# TrinketBlinkM0N.net
KiCad netlist of a schematic drawn in EAGLE
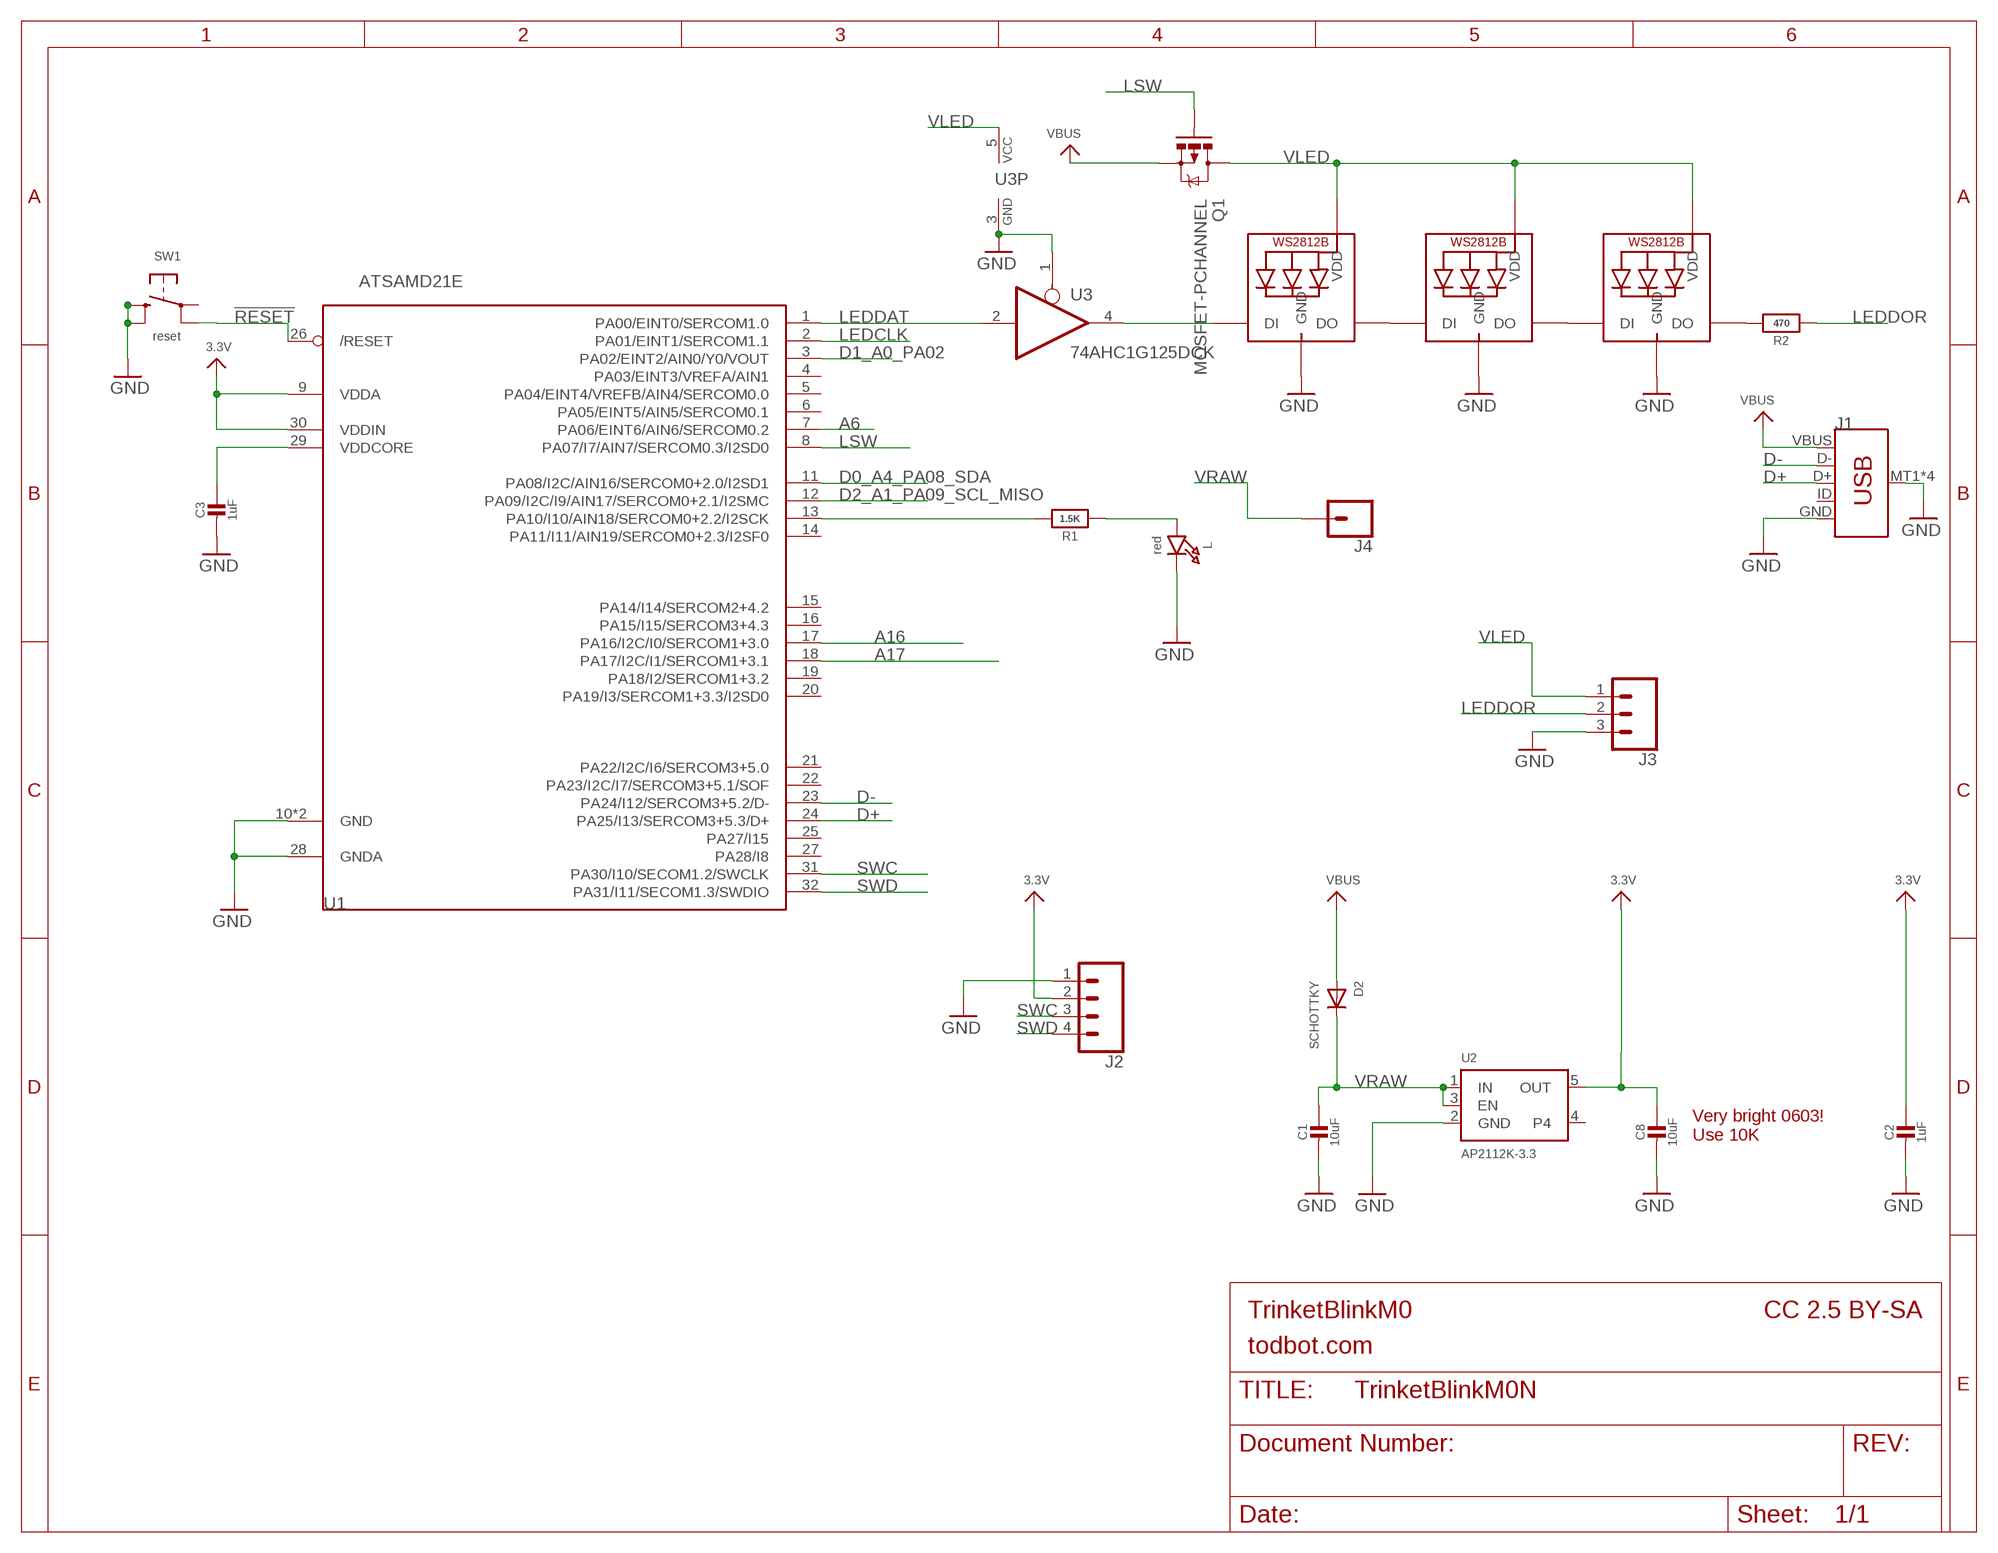
[diagram p0: schematic, sheet 1]

(export (version "E")
  (design (tool "Eeschema 10.0.6"))
  (components
    (comp (ref "C1")
      (value "10uF")
      (footprint "eagle-import:0805-NO")
      (libsource (lib "eagle-import") (part "CAP_CERAMIC0805-NOOUTLINE"))
    )
    (comp (ref "C2")
      (value "1uF")
      (footprint "eagle-import:0603-NO")
      (libsource (lib "eagle-import") (part "CAP_CERAMIC0603_NO"))
    )
    (comp (ref "C3")
      (value "1uF")
      (footprint "eagle-import:0603-NO")
      (libsource (lib "eagle-import") (part "CAP_CERAMIC0603_NO"))
    )
    (comp (ref "C8")
      (value "10uF")
      (footprint "eagle-import:0805-NO")
      (libsource (lib "eagle-import") (part "CAP_CERAMIC0805-NOOUTLINE"))
    )
    (comp (ref "D2")
      (value "SCHOTTKY")
      (footprint "eagle-import:SOD-123FL")
      (libsource (lib "eagle-import") (part "DIODE_SOD-123FL"))
    )
    (comp (ref "J1")
      (value "USB_MICRO-B_SMT")
      (footprint "eagle-import:USB-MICROB")
      (libsource (lib "eagle-import") (part "USB_MICRO-B_SMT"))
    )
    (comp (ref "J2")
      (value "CONN_04")
      (footprint "eagle-import:1X04")
      (libsource (lib "eagle-import") (part "CONN_04"))
    )
    (comp (ref "J3")
      (value "CONN_03")
      (footprint "eagle-import:1X03")
      (libsource (lib "eagle-import") (part "CONN_03"))
    )
    (comp (ref "J4")
      (value "CONN_01")
      (footprint "eagle-import:1X01")
      (libsource (lib "eagle-import") (part "CONN_01"))
    )
    (comp (ref "L")
      (value "red")
      (footprint "eagle-import:CHIPLED_0603_NOOUTLINE")
      (libsource (lib "eagle-import") (part "LED0603_NOOUTLINE"))
    )
    (comp (ref "LED1")
      (value "WS2812B3535")
      (footprint "eagle-import:LED3535")
      (libsource (lib "eagle-import") (part "WS2812B3535"))
    )
    (comp (ref "LED2")
      (value "WS2812B3535")
      (footprint "eagle-import:LED3535")
      (libsource (lib "eagle-import") (part "WS2812B3535"))
    )
    (comp (ref "LED3")
      (value "WS2812B3535")
      (footprint "eagle-import:LED3535")
      (libsource (lib "eagle-import") (part "WS2812B3535"))
    )
    (comp (ref "Q1")
      (value "MOSFET-PCHANNEL")
      (footprint "eagle-import:SOT23-3")
      (libsource (lib "eagle-import") (part "MOSFET-PCHANNEL"))
    )
    (comp (ref "R1")
      (value "1.5K")
      (footprint "eagle-import:0603-NO")
      (libsource (lib "eagle-import") (part "RESISTOR_0603_NOOUT"))
    )
    (comp (ref "R2")
      (value "470")
      (footprint "eagle-import:0603-NO")
      (libsource (lib "eagle-import") (part "RESISTOR_0603_NOOUT"))
    )
    (comp (ref "SW1")
      (value "reset")
      (footprint "eagle-import:BTN_KMR2_4.6X2.8")
      (libsource (lib "eagle-import") (part "SWITCH_TACT_SMT4.6X2.8"))
    )
    (comp (ref "U1")
      (value "ATSAMD21E")
      (footprint "eagle-import:QFN32_5MM")
      (libsource (lib "eagle-import") (part "ATSAMD21E"))
    )
    (comp (ref "U2")
      (value "AP2112K-3.3")
      (footprint "eagle-import:SOT23-5")
      (libsource (lib "eagle-import") (part "VREG_SOT23-5"))
    )
    (comp (ref "U3")
      (value "74AHC1G125DCK")
      (footprint "eagle-import:SC70-5")
      (libsource (lib "eagle-import") (part "741G125DCKAHC"))
    )
  )
  (nets
    (net (code "1") (name "/A6") (class "Default")
      (node (ref "U1") (pin "7") (pinfunction "PA06/EINT6/AIN6/SERCOM0.2_7") (pintype "bidirectional"))
    )
    (net (code "2") (name "/A16") (class "Default")
      (node (ref "U1") (pin "17") (pinfunction "PA16/I2C/I0/SERCOM1+3.0_17") (pintype "bidirectional"))
    )
    (net (code "3") (name "/A17") (class "Default")
      (node (ref "U1") (pin "18") (pinfunction "PA17/I2C/I1/SERCOM1+3.1_18") (pintype "bidirectional"))
    )
    (net (code "4") (name "/D+") (class "Default")
      (node (ref "J1") (pin "D+") (pinfunction "D+_D+") (pintype "bidirectional"))
      (node (ref "U1") (pin "24") (pinfunction "PA25/I13/SERCOM3+5.3/D+_24") (pintype "bidirectional"))
    )
    (net (code "5") (name "/D-") (class "Default")
      (node (ref "J1") (pin "D-") (pinfunction "D-_D-") (pintype "bidirectional"))
      (node (ref "U1") (pin "23") (pinfunction "PA24/I12/SERCOM3+5.2/D-_23") (pintype "bidirectional"))
    )
    (net (code "6") (name "/D0_A4_PA08_SDA") (class "Default")
      (node (ref "U1") (pin "11") (pinfunction "PA08/I2C/AIN16/SERCOM0+2.0/I2SD1_11") (pintype "bidirectional"))
    )
    (net (code "7") (name "/D1_A0_PA02") (class "Default")
      (node (ref "U1") (pin "3") (pinfunction "PA02/EINT2/AIN0/Y0/VOUT_3") (pintype "bidirectional"))
    )
    (net (code "8") (name "/D2_A1_PA09_SCL_MISO") (class "Default")
      (node (ref "U1") (pin "12") (pinfunction "PA09/I2C/I9/AIN17/SERCOM0+2.1/I2SMC_12") (pintype "bidirectional"))
    )
    (net (code "9") (name "/LEDCLK") (class "Default")
      (node (ref "U1") (pin "2") (pinfunction "PA01/EINT1/SERCOM1.1_2") (pintype "bidirectional"))
    )
    (net (code "10") (name "/LEDDAT") (class "Default")
      (node (ref "U1") (pin "1") (pinfunction "PA00/EINT0/SERCOM1.0_1") (pintype "bidirectional"))
      (node (ref "U3") (pin "2") (pinfunction "I_2") (pintype "input"))
    )
    (net (code "11") (name "/LEDDOR") (class "Default")
      (node (ref "J3") (pin "2") (pinfunction "2_2") (pintype "passive"))
      (node (ref "R2") (pin "1") (pinfunction "1_1") (pintype "passive"))
    )
    (net (code "12") (name "/LSW") (class "Default")
      (node (ref "Q1") (pin "1") (pinfunction "G_1") (pintype "passive"))
      (node (ref "U1") (pin "8") (pinfunction "PA07/I7/AIN7/SERCOM0.3/I2SD0_8") (pintype "bidirectional"))
    )
    (net (code "13") (name "/SWC") (class "Default")
      (node (ref "J2") (pin "3") (pinfunction "3_3") (pintype "passive"))
      (node (ref "U1") (pin "31") (pinfunction "PA30/I10/SECOM1.2/SWCLK_31") (pintype "bidirectional"))
    )
    (net (code "14") (name "/SWD") (class "Default")
      (node (ref "J2") (pin "4") (pinfunction "4_4") (pintype "passive"))
      (node (ref "U1") (pin "32") (pinfunction "PA31/I11/SECOM1.3/SWDIO_32") (pintype "bidirectional"))
    )
    (net (code "15") (name "/VLED") (class "Default")
      (node (ref "J3") (pin "1") (pinfunction "1_1") (pintype "passive"))
      (node (ref "LED1") (pin "2") (pinfunction "VDD_2") (pintype "power_in"))
      (node (ref "LED2") (pin "2") (pinfunction "VDD_2") (pintype "power_in"))
      (node (ref "LED3") (pin "2") (pinfunction "VDD_2") (pintype "power_in"))
      (node (ref "Q1") (pin "3") (pinfunction "D_3") (pintype "passive"))
      (node (ref "U3") (pin "5") (pinfunction "VCC_5") (pintype "power_in"))
    )
    (net (code "16") (name "/VRAW") (class "Default")
      (node (ref "C1") (pin "1") (pinfunction "1_1") (pintype "passive"))
      (node (ref "D2") (pin "C") (pinfunction "C_C") (pintype "passive"))
      (node (ref "J4") (pin "1") (pinfunction "1_1") (pintype "passive"))
      (node (ref "U2") (pin "1") (pinfunction "IN_1") (pintype "power_in"))
      (node (ref "U2") (pin "3") (pinfunction "EN_3") (pintype "input"))
    )
    (net (code "17") (name "/~{RESET}") (class "Default")
      (node (ref "SW1") (pin "A'") (pinfunction "P1_A'") (pintype "passive"))
      (node (ref "U1") (pin "26") (pinfunction "/RESET_26") (pintype "bidirectional"))
    )
    (net (code "18") (name "3.3V") (class "Default")
      (node (ref "C2") (pin "1") (pinfunction "1_1") (pintype "passive"))
      (node (ref "C8") (pin "1") (pinfunction "1_1") (pintype "passive"))
      (node (ref "J2") (pin "2") (pinfunction "2_2") (pintype "passive"))
      (node (ref "U1") (pin "30") (pinfunction "VDDIN_30") (pintype "power_in"))
      (node (ref "U1") (pin "9") (pinfunction "VDDA_9") (pintype "power_in"))
      (node (ref "U2") (pin "5") (pinfunction "OUT_5") (pintype "power_in"))
    )
    (net (code "19") (name "GND") (class "Default")
      (node (ref "C1") (pin "2") (pinfunction "2_2") (pintype "passive"))
      (node (ref "C2") (pin "2") (pinfunction "2_2") (pintype "passive"))
      (node (ref "C3") (pin "2") (pinfunction "2_2") (pintype "passive"))
      (node (ref "C8") (pin "2") (pinfunction "2_2") (pintype "passive"))
      (node (ref "J1") (pin "GND") (pinfunction "GND_GND") (pintype "power_in"))
      (node (ref "J1") (pin "MT1") (pinfunction "SHIELD_MT1") (pintype "bidirectional"))
      (node (ref "J1") (pin "MT2") (pinfunction "SHIELD_MT2") (pintype "bidirectional"))
      (node (ref "J1") (pin "P$1") (pinfunction "SHIELD_P$1") (pintype "bidirectional"))
      (node (ref "J1") (pin "P$2") (pinfunction "SHIELD_P$2") (pintype "bidirectional"))
      (node (ref "J2") (pin "1") (pinfunction "1_1") (pintype "passive"))
      (node (ref "J3") (pin "3") (pinfunction "3_3") (pintype "passive"))
      (node (ref "L") (pin "C") (pinfunction "C_C") (pintype "passive"))
      (node (ref "LED1") (pin "4") (pinfunction "GND_4") (pintype "power_in"))
      (node (ref "LED2") (pin "4") (pinfunction "GND_4") (pintype "power_in"))
      (node (ref "LED3") (pin "4") (pinfunction "GND_4") (pintype "power_in"))
      (node (ref "SW1") (pin "B") (pinfunction "S_B") (pintype "passive"))
      (node (ref "SW1") (pin "B'") (pinfunction "S1_B'") (pintype "passive"))
      (node (ref "U1") (pin "10") (pinfunction "GND_10") (pintype "power_in"))
      (node (ref "U1") (pin "28") (pinfunction "GNDA_28") (pintype "power_in"))
      (node (ref "U1") (pin "33") (pinfunction "GND_33") (pintype "power_in"))
      (node (ref "U2") (pin "2") (pinfunction "GND_2") (pintype "power_in"))
      (node (ref "U3") (pin "1") (pinfunction "OE_1") (pintype "input"))
      (node (ref "U3") (pin "3") (pinfunction "GND_3") (pintype "power_in"))
    )
    (net (code "20") (name "Net-(L-PadA)") (class "Default")
      (node (ref "L") (pin "A") (pinfunction "A_A") (pintype "passive"))
      (node (ref "R1") (pin "1") (pinfunction "1_1") (pintype "passive"))
    )
    (net (code "21") (name "Net-(LED1-DI)") (class "Default")
      (node (ref "LED1") (pin "1") (pinfunction "DI_1") (pintype "input"))
      (node (ref "U3") (pin "4") (pinfunction "O_4") (pintype "tri_state"))
    )
    (net (code "22") (name "Net-(LED1-DO)") (class "Default")
      (node (ref "LED1") (pin "3") (pinfunction "DO_3") (pintype "output"))
      (node (ref "LED2") (pin "1") (pinfunction "DI_1") (pintype "input"))
    )
    (net (code "23") (name "Net-(LED2-DO)") (class "Default")
      (node (ref "LED2") (pin "3") (pinfunction "DO_3") (pintype "output"))
      (node (ref "LED3") (pin "1") (pinfunction "DI_1") (pintype "input"))
    )
    (net (code "24") (name "Net-(LED3-DO)") (class "Default")
      (node (ref "LED3") (pin "3") (pinfunction "DO_3") (pintype "output"))
      (node (ref "R2") (pin "2") (pinfunction "2_2") (pintype "passive"))
    )
    (net (code "25") (name "Net-(U1-PA10{slash}I10{slash}AIN18{slash}SERCOM0+2.2{slash}I2SCK)") (class "Default")
      (node (ref "R1") (pin "2") (pinfunction "2_2") (pintype "passive"))
      (node (ref "U1") (pin "13") (pinfunction "PA10/I10/AIN18/SERCOM0+2.2/I2SCK_13") (pintype "bidirectional"))
    )
    (net (code "26") (name "Net-(U1-VDDCORE)") (class "Default")
      (node (ref "C3") (pin "1") (pinfunction "1_1") (pintype "passive"))
      (node (ref "U1") (pin "29") (pinfunction "VDDCORE_29") (pintype "power_in"))
    )
    (net (code "27") (name "VBUS") (class "Default")
      (node (ref "D2") (pin "A") (pinfunction "A_A") (pintype "passive"))
      (node (ref "J1") (pin "VBUS") (pinfunction "VBUS_VBUS") (pintype "power_in"))
      (node (ref "Q1") (pin "2") (pinfunction "S_2") (pintype "passive"))
    )
    (net (code "28") (name "unconnected-(J1-PadID)") (class "Default")
      (node (ref "J1") (pin "ID") (pinfunction "ID_ID") (pintype "bidirectional"))
    )
    (net (code "29") (name "unconnected-(SW1-P-PadA)") (class "Default")
      (node (ref "SW1") (pin "A") (pinfunction "P_A") (pintype "passive"))
    )
    (net (code "30") (name "unconnected-(U1-PA03{slash}EINT3{slash}VREFA{slash}AIN1-Pad4)") (class "Default")
      (node (ref "U1") (pin "4") (pinfunction "PA03/EINT3/VREFA/AIN1_4") (pintype "bidirectional"))
    )
    (net (code "31") (name "unconnected-(U1-PA04{slash}EINT4{slash}VREFB{slash}AIN4{slash}SERCOM0.0-Pad5)") (class "Default")
      (node (ref "U1") (pin "5") (pinfunction "PA04/EINT4/VREFB/AIN4/SERCOM0.0_5") (pintype "bidirectional"))
    )
    (net (code "32") (name "unconnected-(U1-PA05{slash}EINT5{slash}AIN5{slash}SERCOM0.1-Pad6)") (class "Default")
      (node (ref "U1") (pin "6") (pinfunction "PA05/EINT5/AIN5/SERCOM0.1_6") (pintype "bidirectional"))
    )
    (net (code "33") (name "unconnected-(U1-PA11{slash}I11{slash}AIN19{slash}SERCOM0+2.3{slash}I2SF0-Pad14)") (class "Default")
      (node (ref "U1") (pin "14") (pinfunction "PA11/I11/AIN19/SERCOM0+2.3/I2SF0_14") (pintype "bidirectional"))
    )
    (net (code "34") (name "unconnected-(U1-PA14{slash}I14{slash}SERCOM2+4.2-Pad15)") (class "Default")
      (node (ref "U1") (pin "15") (pinfunction "PA14/I14/SERCOM2+4.2_15") (pintype "bidirectional"))
    )
    (net (code "35") (name "unconnected-(U1-PA15{slash}I15{slash}SERCOM3+4.3-Pad16)") (class "Default")
      (node (ref "U1") (pin "16") (pinfunction "PA15/I15/SERCOM3+4.3_16") (pintype "bidirectional"))
    )
    (net (code "36") (name "unconnected-(U1-PA18{slash}I2{slash}SERCOM1+3.2-Pad19)") (class "Default")
      (node (ref "U1") (pin "19") (pinfunction "PA18/I2/SERCOM1+3.2_19") (pintype "bidirectional"))
    )
    (net (code "37") (name "unconnected-(U1-PA19{slash}I3{slash}SERCOM1+3.3{slash}I2SD0-Pad20)") (class "Default")
      (node (ref "U1") (pin "20") (pinfunction "PA19/I3/SERCOM1+3.3/I2SD0_20") (pintype "bidirectional"))
    )
    (net (code "38") (name "unconnected-(U1-PA22{slash}I2C{slash}I6{slash}SERCOM3+5.0-Pad21)") (class "Default")
      (node (ref "U1") (pin "21") (pinfunction "PA22/I2C/I6/SERCOM3+5.0_21") (pintype "bidirectional"))
    )
    (net (code "39") (name "unconnected-(U1-PA23{slash}I2C{slash}I7{slash}SERCOM3+5.1{slash}SOF-Pad22)") (class "Default")
      (node (ref "U1") (pin "22") (pinfunction "PA23/I2C/I7/SERCOM3+5.1/SOF_22") (pintype "bidirectional"))
    )
    (net (code "40") (name "unconnected-(U1-PA27{slash}I15-Pad25)") (class "Default")
      (node (ref "U1") (pin "25") (pinfunction "PA27/I15_25") (pintype "bidirectional"))
    )
    (net (code "41") (name "unconnected-(U1-PA28{slash}I8-Pad27)") (class "Default")
      (node (ref "U1") (pin "27") (pinfunction "PA28/I8_27") (pintype "bidirectional"))
    )
    (net (code "42") (name "unconnected-(U2-P4-Pad4)") (class "Default")
      (node (ref "U2") (pin "4") (pinfunction "P4_4") (pintype "bidirectional"))
    )
  )
)
